# 05A-005.net
KiCad netlist of a schematic drawn in EAGLE
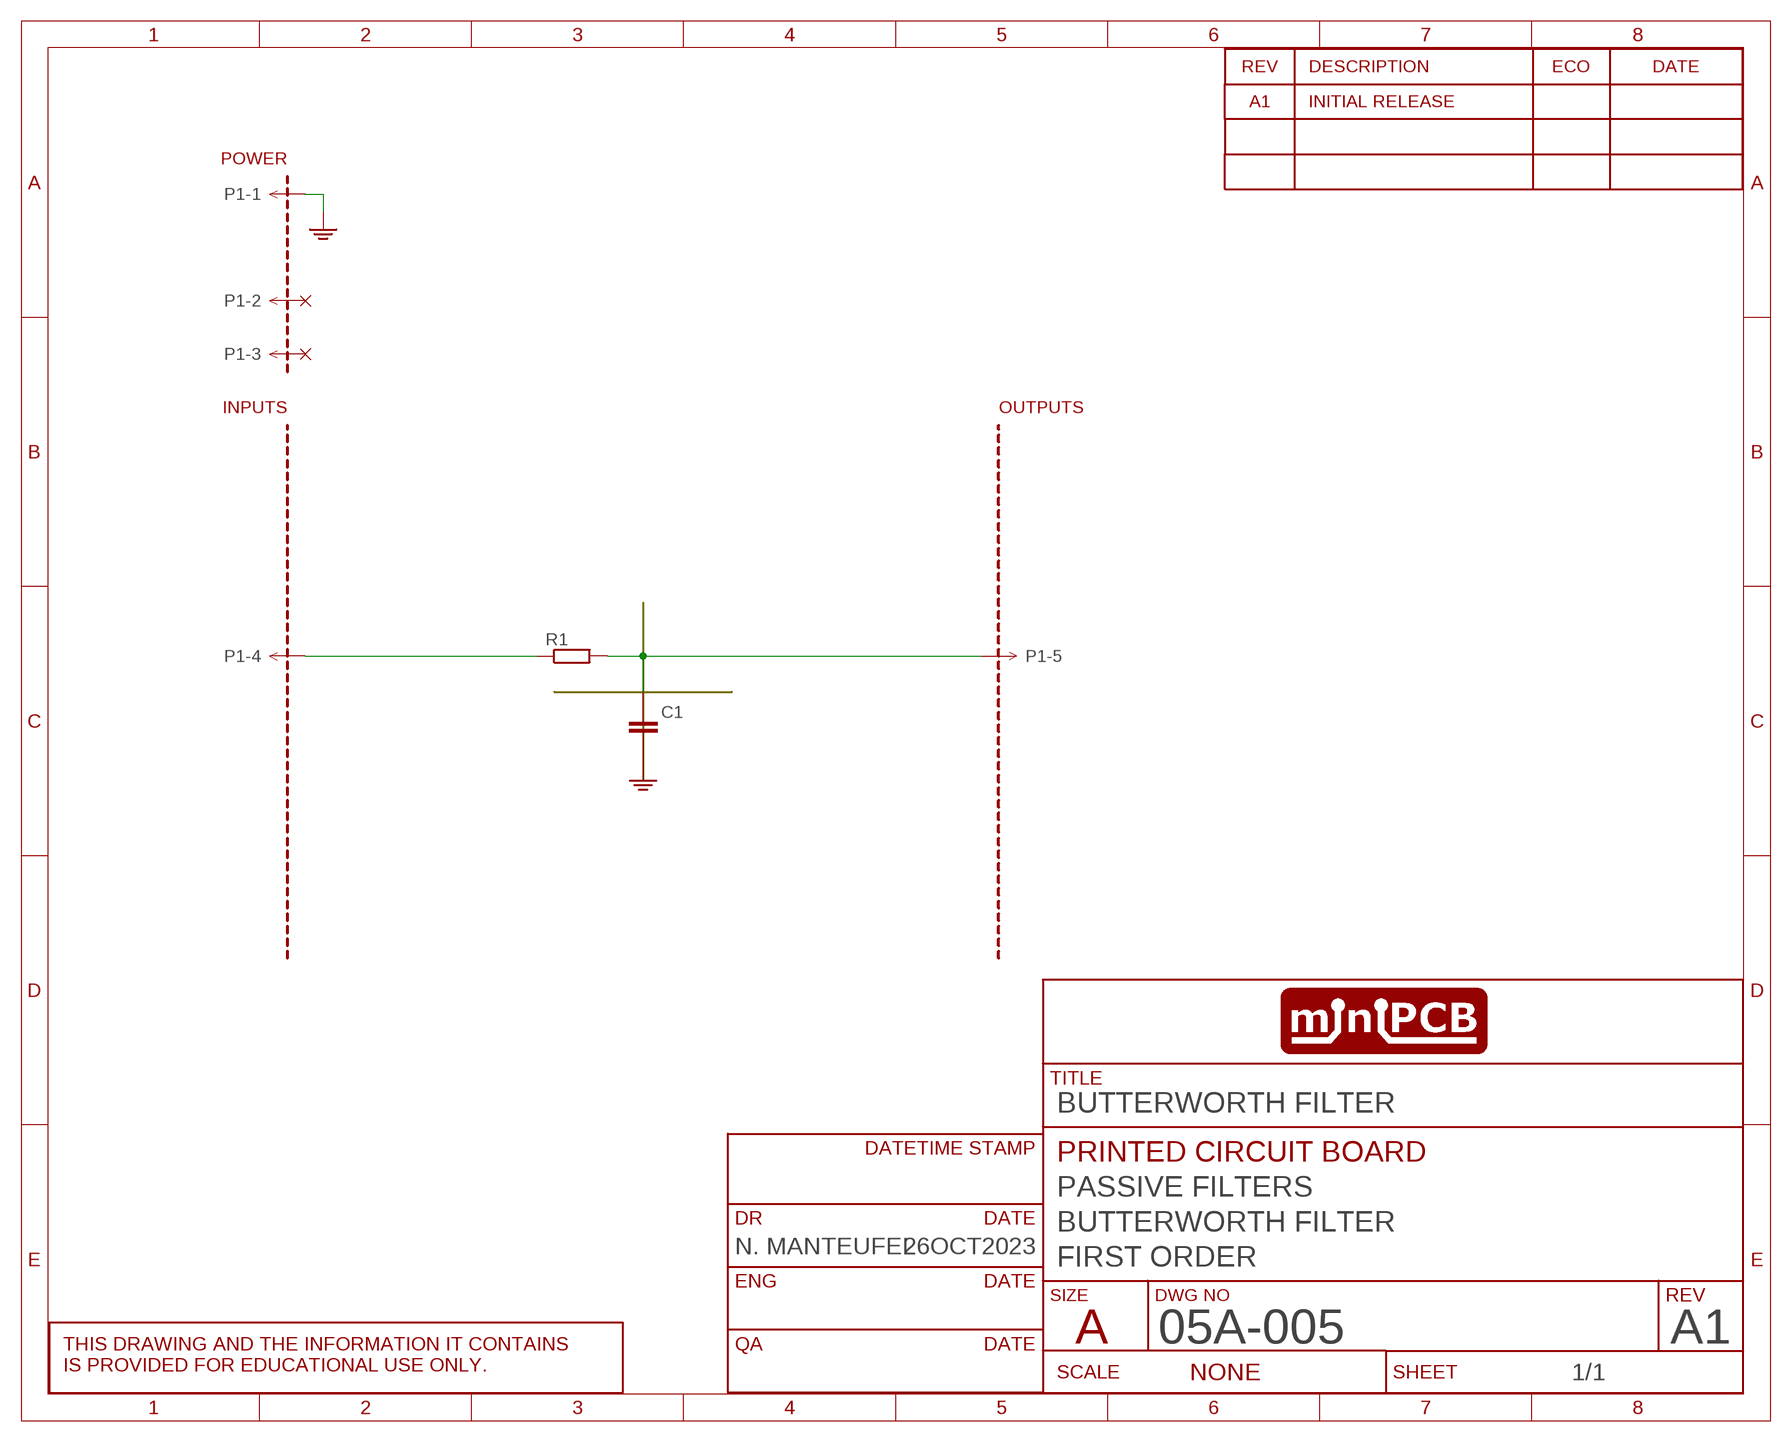
[diagram p0: schematic, sheet 1]

(export (version "E")
  (design (tool "Eeschema 10.0.6"))
  (components
    (comp (ref "C1")
      (value "CAPACITORTHD")
      (footprint "eagle-import:C050-024X044")
      (libsource (lib "eagle-import") (part "CAPACITORTHD"))
    )
    (comp (ref "P1")
      (value "MINIPCB_5P5P")
      (footprint "eagle-import:PINS_1X5")
      (libsource (lib "eagle-import") (part "MINIPCB_5P5P"))
    )
    (comp (ref "PCB1")
      (value "MINIPCB_0P00A-20X25")
      (footprint "eagle-import:MINIPCB_00A_20X25")
      (libsource (lib "eagle-import") (part "MINIPCB_0P00A-20X25"))
    )
    (comp (ref "R1")
      (value "RESISTORTHD")
      (footprint "eagle-import:0204_10")
      (libsource (lib "eagle-import") (part "RESISTORTHD"))
    )
  )
  (nets
    (net (code "1") (name "GND") (class "Default")
      (node (ref "C1") (pin "2") (pinfunction "-_2") (pintype "passive"))
      (node (ref "P1") (pin "1") (pinfunction "1_1") (pintype "bidirectional"))
    )
    (net (code "2") (name "Net-(C1-+)") (class "Default")
      (node (ref "C1") (pin "1") (pinfunction "+_1") (pintype "passive"))
      (node (ref "P1") (pin "5") (pinfunction "1_5") (pintype "bidirectional"))
      (node (ref "R1") (pin "2") (pinfunction "2_2") (pintype "passive"))
    )
    (net (code "3") (name "Net-(P1D-1)") (class "Default")
      (node (ref "P1") (pin "4") (pinfunction "1_4") (pintype "bidirectional"))
      (node (ref "R1") (pin "1") (pinfunction "1_1") (pintype "passive"))
    )
    (net (code "4") (name "unconnected-(P1B-1-Pad2)") (class "Default")
      (node (ref "P1") (pin "2") (pinfunction "1_2") (pintype "bidirectional"))
    )
    (net (code "5") (name "unconnected-(P1C-1-Pad3)") (class "Default")
      (node (ref "P1") (pin "3") (pinfunction "1_3") (pintype "bidirectional"))
    )
  )
)
